# meow-65.net
KiCad netlist of a schematic drawn in Altium Designer
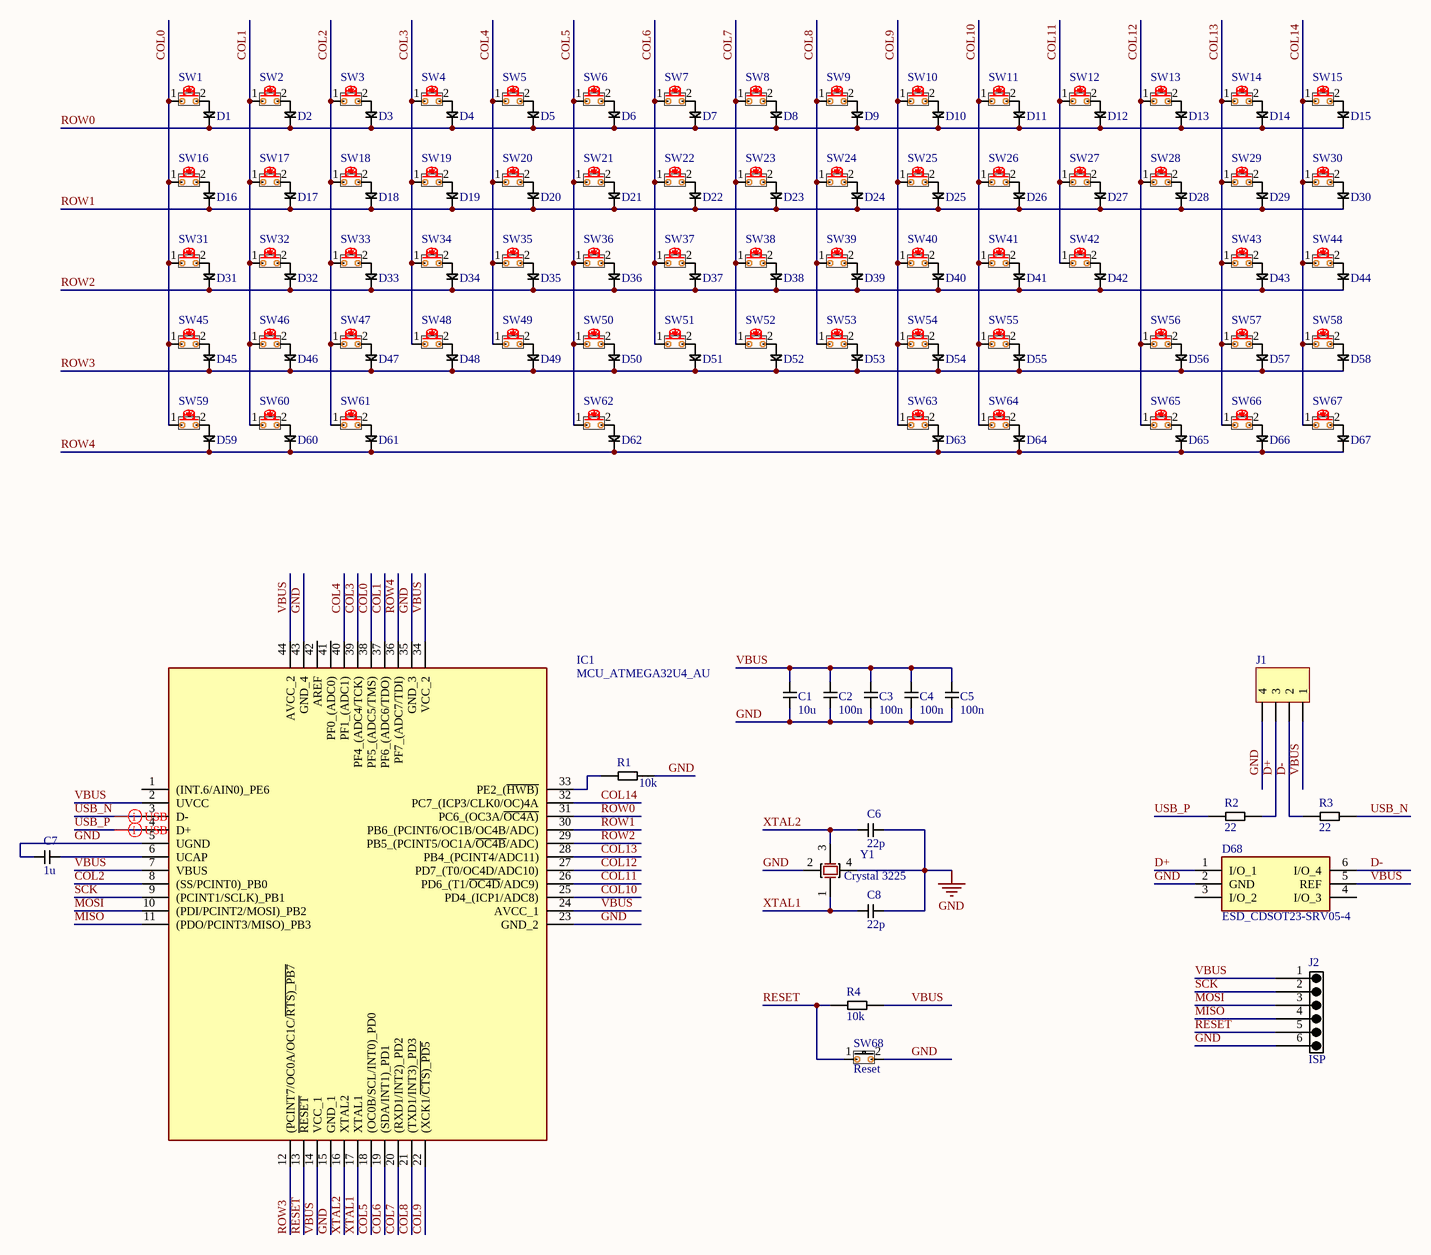
[diagram p0: meow-65.SchDoc]

(export (version "E")
  (design (tool "Eeschema 10.0.6"))
  (components
    (comp (ref "C1") (value "10u") (footprint "CAP_0805") (libsource (lib "Keyboard") (part "CAP_0805")))
    (comp (ref "C2") (value "100n") (footprint "CAP_0805") (libsource (lib "Keyboard") (part "CAP_0805")))
    (comp (ref "C3") (value "100n") (footprint "CAP_0805") (libsource (lib "Keyboard") (part "CAP_0805")))
    (comp (ref "C4") (value "100n") (footprint "CAP_0805") (libsource (lib "Keyboard") (part "CAP_0805")))
    (comp (ref "C5") (value "100n") (footprint "CAP_0805") (libsource (lib "Keyboard") (part "CAP_0805")))
    (comp (ref "C6") (value "22p") (footprint "CAP_0805") (libsource (lib "Keyboard") (part "CAP_0805")))
    (comp (ref "C7") (value "1u") (footprint "CAP_0805") (libsource (lib "Keyboard") (part "CAP_0805")))
    (comp (ref "C8") (value "22p") (footprint "CAP_0805") (libsource (lib "Keyboard") (part "CAP_0805")))
    (comp (ref "D1")
      (value "1N4148_SOD123")
      (footprint "SOD123")
      (libsource (lib "Keyboard") (part "1N4148_SOD123"))
    )
    (comp (ref "D2")
      (value "1N4148_SOD123")
      (footprint "SOD123")
      (libsource (lib "Keyboard") (part "1N4148_SOD123"))
    )
    (comp (ref "D3")
      (value "1N4148_SOD123")
      (footprint "SOD123")
      (libsource (lib "Keyboard") (part "1N4148_SOD123"))
    )
    (comp (ref "D4")
      (value "1N4148_SOD123")
      (footprint "SOD123")
      (libsource (lib "Keyboard") (part "1N4148_SOD123"))
    )
    (comp (ref "D5")
      (value "1N4148_SOD123")
      (footprint "SOD123")
      (libsource (lib "Keyboard") (part "1N4148_SOD123"))
    )
    (comp (ref "D6")
      (value "1N4148_SOD123")
      (footprint "SOD123")
      (libsource (lib "Keyboard") (part "1N4148_SOD123"))
    )
    (comp (ref "D7")
      (value "1N4148_SOD123")
      (footprint "SOD123")
      (libsource (lib "Keyboard") (part "1N4148_SOD123"))
    )
    (comp (ref "D8")
      (value "1N4148_SOD123")
      (footprint "SOD123")
      (libsource (lib "Keyboard") (part "1N4148_SOD123"))
    )
    (comp (ref "D9")
      (value "1N4148_SOD123")
      (footprint "SOD123")
      (libsource (lib "Keyboard") (part "1N4148_SOD123"))
    )
    (comp (ref "D10")
      (value "1N4148_SOD123")
      (footprint "SOD123")
      (libsource (lib "Keyboard") (part "1N4148_SOD123"))
    )
    (comp (ref "D11")
      (value "1N4148_SOD123")
      (footprint "SOD123")
      (libsource (lib "Keyboard") (part "1N4148_SOD123"))
    )
    (comp (ref "D12")
      (value "1N4148_SOD123")
      (footprint "SOD123")
      (libsource (lib "Keyboard") (part "1N4148_SOD123"))
    )
    (comp (ref "D13")
      (value "1N4148_SOD123")
      (footprint "SOD123")
      (libsource (lib "Keyboard") (part "1N4148_SOD123"))
    )
    (comp (ref "D14")
      (value "1N4148_SOD123")
      (footprint "SOD123")
      (libsource (lib "Keyboard") (part "1N4148_SOD123"))
    )
    (comp (ref "D15")
      (value "1N4148_SOD123")
      (footprint "SOD123")
      (libsource (lib "Keyboard") (part "1N4148_SOD123"))
    )
    (comp (ref "D16")
      (value "1N4148_SOD123")
      (footprint "SOD123")
      (libsource (lib "Keyboard") (part "1N4148_SOD123"))
    )
    (comp (ref "D17")
      (value "1N4148_SOD123")
      (footprint "SOD123")
      (libsource (lib "Keyboard") (part "1N4148_SOD123"))
    )
    (comp (ref "D18")
      (value "1N4148_SOD123")
      (footprint "SOD123")
      (libsource (lib "Keyboard") (part "1N4148_SOD123"))
    )
    (comp (ref "D19")
      (value "1N4148_SOD123")
      (footprint "SOD123")
      (libsource (lib "Keyboard") (part "1N4148_SOD123"))
    )
    (comp (ref "D20")
      (value "1N4148_SOD123")
      (footprint "SOD123")
      (libsource (lib "Keyboard") (part "1N4148_SOD123"))
    )
    (comp (ref "D21")
      (value "1N4148_SOD123")
      (footprint "SOD123")
      (libsource (lib "Keyboard") (part "1N4148_SOD123"))
    )
    (comp (ref "D22")
      (value "1N4148_SOD123")
      (footprint "SOD123")
      (libsource (lib "Keyboard") (part "1N4148_SOD123"))
    )
    (comp (ref "D23")
      (value "1N4148_SOD123")
      (footprint "SOD123")
      (libsource (lib "Keyboard") (part "1N4148_SOD123"))
    )
    (comp (ref "D24")
      (value "1N4148_SOD123")
      (footprint "SOD123")
      (libsource (lib "Keyboard") (part "1N4148_SOD123"))
    )
    (comp (ref "D25")
      (value "1N4148_SOD123")
      (footprint "SOD123")
      (libsource (lib "Keyboard") (part "1N4148_SOD123"))
    )
    (comp (ref "D26")
      (value "1N4148_SOD123")
      (footprint "SOD123")
      (libsource (lib "Keyboard") (part "1N4148_SOD123"))
    )
    (comp (ref "D27")
      (value "1N4148_SOD123")
      (footprint "SOD123")
      (libsource (lib "Keyboard") (part "1N4148_SOD123"))
    )
    (comp (ref "D28")
      (value "1N4148_SOD123")
      (footprint "SOD123")
      (libsource (lib "Keyboard") (part "1N4148_SOD123"))
    )
    (comp (ref "D29")
      (value "1N4148_SOD123")
      (footprint "SOD123")
      (libsource (lib "Keyboard") (part "1N4148_SOD123"))
    )
    (comp (ref "D30")
      (value "1N4148_SOD123")
      (footprint "SOD123")
      (libsource (lib "Keyboard") (part "1N4148_SOD123"))
    )
    (comp (ref "D31")
      (value "1N4148_SOD123")
      (footprint "SOD123")
      (libsource (lib "Keyboard") (part "1N4148_SOD123"))
    )
    (comp (ref "D32")
      (value "1N4148_SOD123")
      (footprint "SOD123")
      (libsource (lib "Keyboard") (part "1N4148_SOD123"))
    )
    (comp (ref "D33")
      (value "1N4148_SOD123")
      (footprint "SOD123")
      (libsource (lib "Keyboard") (part "1N4148_SOD123"))
    )
    (comp (ref "D34")
      (value "1N4148_SOD123")
      (footprint "SOD123")
      (libsource (lib "Keyboard") (part "1N4148_SOD123"))
    )
    (comp (ref "D35")
      (value "1N4148_SOD123")
      (footprint "SOD123")
      (libsource (lib "Keyboard") (part "1N4148_SOD123"))
    )
    (comp (ref "D36")
      (value "1N4148_SOD123")
      (footprint "SOD123")
      (libsource (lib "Keyboard") (part "1N4148_SOD123"))
    )
    (comp (ref "D37")
      (value "1N4148_SOD123")
      (footprint "SOD123")
      (libsource (lib "Keyboard") (part "1N4148_SOD123"))
    )
    (comp (ref "D38")
      (value "1N4148_SOD123")
      (footprint "SOD123")
      (libsource (lib "Keyboard") (part "1N4148_SOD123"))
    )
    (comp (ref "D39")
      (value "1N4148_SOD123")
      (footprint "SOD123")
      (libsource (lib "Keyboard") (part "1N4148_SOD123"))
    )
    (comp (ref "D40")
      (value "1N4148_SOD123")
      (footprint "SOD123")
      (libsource (lib "Keyboard") (part "1N4148_SOD123"))
    )
    (comp (ref "D41")
      (value "1N4148_SOD123")
      (footprint "SOD123")
      (libsource (lib "Keyboard") (part "1N4148_SOD123"))
    )
    (comp (ref "D42")
      (value "1N4148_SOD123")
      (footprint "SOD123")
      (libsource (lib "Keyboard") (part "1N4148_SOD123"))
    )
    (comp (ref "D43")
      (value "1N4148_SOD123")
      (footprint "SOD123")
      (libsource (lib "Keyboard") (part "1N4148_SOD123"))
    )
    (comp (ref "D44")
      (value "1N4148_SOD123")
      (footprint "SOD123")
      (libsource (lib "Keyboard") (part "1N4148_SOD123"))
    )
    (comp (ref "D45")
      (value "1N4148_SOD123")
      (footprint "SOD123")
      (libsource (lib "Keyboard") (part "1N4148_SOD123"))
    )
    (comp (ref "D46")
      (value "1N4148_SOD123")
      (footprint "SOD123")
      (libsource (lib "Keyboard") (part "1N4148_SOD123"))
    )
    (comp (ref "D47")
      (value "1N4148_SOD123")
      (footprint "SOD123")
      (libsource (lib "Keyboard") (part "1N4148_SOD123"))
    )
    (comp (ref "D48")
      (value "1N4148_SOD123")
      (footprint "SOD123")
      (libsource (lib "Keyboard") (part "1N4148_SOD123"))
    )
    (comp (ref "D49")
      (value "1N4148_SOD123")
      (footprint "SOD123")
      (libsource (lib "Keyboard") (part "1N4148_SOD123"))
    )
    (comp (ref "D50")
      (value "1N4148_SOD123")
      (footprint "SOD123")
      (libsource (lib "Keyboard") (part "1N4148_SOD123"))
    )
    (comp (ref "D51")
      (value "1N4148_SOD123")
      (footprint "SOD123")
      (libsource (lib "Keyboard") (part "1N4148_SOD123"))
    )
    (comp (ref "D52")
      (value "1N4148_SOD123")
      (footprint "SOD123")
      (libsource (lib "Keyboard") (part "1N4148_SOD123"))
    )
    (comp (ref "D53")
      (value "1N4148_SOD123")
      (footprint "SOD123")
      (libsource (lib "Keyboard") (part "1N4148_SOD123"))
    )
    (comp (ref "D54")
      (value "1N4148_SOD123")
      (footprint "SOD123")
      (libsource (lib "Keyboard") (part "1N4148_SOD123"))
    )
    (comp (ref "D55")
      (value "1N4148_SOD123")
      (footprint "SOD123")
      (libsource (lib "Keyboard") (part "1N4148_SOD123"))
    )
    (comp (ref "D56")
      (value "1N4148_SOD123")
      (footprint "SOD123")
      (libsource (lib "Keyboard") (part "1N4148_SOD123"))
    )
    (comp (ref "D57")
      (value "1N4148_SOD123")
      (footprint "SOD123")
      (libsource (lib "Keyboard") (part "1N4148_SOD123"))
    )
    (comp (ref "D58")
      (value "1N4148_SOD123")
      (footprint "SOD123")
      (libsource (lib "Keyboard") (part "1N4148_SOD123"))
    )
    (comp (ref "D59")
      (value "1N4148_SOD123")
      (footprint "SOD123")
      (libsource (lib "Keyboard") (part "1N4148_SOD123"))
    )
    (comp (ref "D60")
      (value "1N4148_SOD123")
      (footprint "SOD123")
      (libsource (lib "Keyboard") (part "1N4148_SOD123"))
    )
    (comp (ref "D61")
      (value "1N4148_SOD123")
      (footprint "SOD123")
      (libsource (lib "Keyboard") (part "1N4148_SOD123"))
    )
    (comp (ref "D62")
      (value "1N4148_SOD123")
      (footprint "SOD123")
      (libsource (lib "Keyboard") (part "1N4148_SOD123"))
    )
    (comp (ref "D63")
      (value "1N4148_SOD123")
      (footprint "SOD123")
      (libsource (lib "Keyboard") (part "1N4148_SOD123"))
    )
    (comp (ref "D64")
      (value "1N4148_SOD123")
      (footprint "SOD123")
      (libsource (lib "Keyboard") (part "1N4148_SOD123"))
    )
    (comp (ref "D65")
      (value "1N4148_SOD123")
      (footprint "SOD123")
      (libsource (lib "Keyboard") (part "1N4148_SOD123"))
    )
    (comp (ref "D66")
      (value "1N4148_SOD123")
      (footprint "SOD123")
      (libsource (lib "Keyboard") (part "1N4148_SOD123"))
    )
    (comp (ref "D67")
      (value "1N4148_SOD123")
      (footprint "SOD123")
      (libsource (lib "Keyboard") (part "1N4148_SOD123"))
    )
    (comp (ref "D68")
      (value "ESD_CDSOT23-SRV05-4")
      (footprint "SOT23_6")
      (libsource (lib "Keyboard") (part "ESD_CDSOT23-SRV05-4"))
    )
    (comp (ref "IC1")
      (value "MCU_ATMEGA32U4_AU")
      (footprint "44-TQFP")
      (libsource (lib "Keyboard") (part "MCU_ATMEGA32U4_AU"))
    )
    (comp (ref "J1")
      (value "SM04B-SRSS-TB(LF)(SN)")
      (footprint "JP_1.0_4P")
      (libsource (lib "Keyboard") (part "JP_1.0_4P"))
    )
    (comp (ref "J2")
      (value "ISP")
      (footprint "JP_2.54_6P_NoJump")
      (libsource (lib "Keyboard") (part "JP_2.54_6P_NoJump"))
    )
    (comp (ref "R1") (value "10k") (footprint "RES_0805") (libsource (lib "Keyboard") (part "RES_0805")))
    (comp (ref "R2") (value "22") (footprint "RES_0805") (libsource (lib "Keyboard") (part "RES_0805")))
    (comp (ref "R3") (value "22") (footprint "RES_0805") (libsource (lib "Keyboard") (part "RES_0805")))
    (comp (ref "R4") (value "10k") (footprint "RES_0805") (libsource (lib "Keyboard") (part "RES_0805")))
    (comp (ref "SW1") (value "MX_HS") (footprint "MX_HS") (libsource (lib "Keyboard") (part "MX_HS")))
    (comp (ref "SW2") (value "MX_HS") (footprint "MX_HS") (libsource (lib "Keyboard") (part "MX_HS")))
    (comp (ref "SW3") (value "MX_HS") (footprint "MX_HS") (libsource (lib "Keyboard") (part "MX_HS")))
    (comp (ref "SW4") (value "MX_HS") (footprint "MX_HS") (libsource (lib "Keyboard") (part "MX_HS")))
    (comp (ref "SW5") (value "MX_HS") (footprint "MX_HS") (libsource (lib "Keyboard") (part "MX_HS")))
    (comp (ref "SW6") (value "MX_HS") (footprint "MX_HS") (libsource (lib "Keyboard") (part "MX_HS")))
    (comp (ref "SW7") (value "MX_HS") (footprint "MX_HS") (libsource (lib "Keyboard") (part "MX_HS")))
    (comp (ref "SW8") (value "MX_HS") (footprint "MX_HS") (libsource (lib "Keyboard") (part "MX_HS")))
    (comp (ref "SW9") (value "MX_HS") (footprint "MX_HS") (libsource (lib "Keyboard") (part "MX_HS")))
    (comp (ref "SW10") (value "MX_HS") (footprint "MX_HS") (libsource (lib "Keyboard") (part "MX_HS")))
    (comp (ref "SW11") (value "MX_HS") (footprint "MX_HS") (libsource (lib "Keyboard") (part "MX_HS")))
    (comp (ref "SW12") (value "MX_HS") (footprint "MX_HS") (libsource (lib "Keyboard") (part "MX_HS")))
    (comp (ref "SW13") (value "MX_HS") (footprint "MX_HS") (libsource (lib "Keyboard") (part "MX_HS")))
    (comp (ref "SW14")
      (value "MX_HS_2U")
      (footprint "MX_HS_2U")
      (libsource (lib "Keyboard") (part "MX_HS_2U"))
    )
    (comp (ref "SW15") (value "MX_HS") (footprint "MX_HS") (libsource (lib "Keyboard") (part "MX_HS")))
    (comp (ref "SW16") (value "MX_HS") (footprint "MX_HS") (libsource (lib "Keyboard") (part "MX_HS")))
    (comp (ref "SW17") (value "MX_HS") (footprint "MX_HS") (libsource (lib "Keyboard") (part "MX_HS")))
    (comp (ref "SW18") (value "MX_HS") (footprint "MX_HS") (libsource (lib "Keyboard") (part "MX_HS")))
    (comp (ref "SW19") (value "MX_HS") (footprint "MX_HS") (libsource (lib "Keyboard") (part "MX_HS")))
    (comp (ref "SW20") (value "MX_HS") (footprint "MX_HS") (libsource (lib "Keyboard") (part "MX_HS")))
    (comp (ref "SW21") (value "MX_HS") (footprint "MX_HS") (libsource (lib "Keyboard") (part "MX_HS")))
    (comp (ref "SW22") (value "MX_HS") (footprint "MX_HS") (libsource (lib "Keyboard") (part "MX_HS")))
    (comp (ref "SW23") (value "MX_HS") (footprint "MX_HS") (libsource (lib "Keyboard") (part "MX_HS")))
    (comp (ref "SW24") (value "MX_HS") (footprint "MX_HS") (libsource (lib "Keyboard") (part "MX_HS")))
    (comp (ref "SW25") (value "MX_HS") (footprint "MX_HS") (libsource (lib "Keyboard") (part "MX_HS")))
    (comp (ref "SW26") (value "MX_HS") (footprint "MX_HS") (libsource (lib "Keyboard") (part "MX_HS")))
    (comp (ref "SW27") (value "MX_HS") (footprint "MX_HS") (libsource (lib "Keyboard") (part "MX_HS")))
    (comp (ref "SW28") (value "MX_HS") (footprint "MX_HS") (libsource (lib "Keyboard") (part "MX_HS")))
    (comp (ref "SW29") (value "MX_HS") (footprint "MX_HS") (libsource (lib "Keyboard") (part "MX_HS")))
    (comp (ref "SW30") (value "MX_HS") (footprint "MX_HS") (libsource (lib "Keyboard") (part "MX_HS")))
    (comp (ref "SW31") (value "MX_HS") (footprint "MX_HS") (libsource (lib "Keyboard") (part "MX_HS")))
    (comp (ref "SW32") (value "MX_HS") (footprint "MX_HS") (libsource (lib "Keyboard") (part "MX_HS")))
    (comp (ref "SW33") (value "MX_HS") (footprint "MX_HS") (libsource (lib "Keyboard") (part "MX_HS")))
    (comp (ref "SW34") (value "MX_HS") (footprint "MX_HS") (libsource (lib "Keyboard") (part "MX_HS")))
    (comp (ref "SW35") (value "MX_HS") (footprint "MX_HS") (libsource (lib "Keyboard") (part "MX_HS")))
    (comp (ref "SW36") (value "MX_HS") (footprint "MX_HS") (libsource (lib "Keyboard") (part "MX_HS")))
    (comp (ref "SW37") (value "MX_HS") (footprint "MX_HS") (libsource (lib "Keyboard") (part "MX_HS")))
    (comp (ref "SW38") (value "MX_HS") (footprint "MX_HS") (libsource (lib "Keyboard") (part "MX_HS")))
    (comp (ref "SW39") (value "MX_HS") (footprint "MX_HS") (libsource (lib "Keyboard") (part "MX_HS")))
    (comp (ref "SW40") (value "MX_HS") (footprint "MX_HS") (libsource (lib "Keyboard") (part "MX_HS")))
    (comp (ref "SW41") (value "MX_HS") (footprint "MX_HS") (libsource (lib "Keyboard") (part "MX_HS")))
    (comp (ref "SW42") (value "MX_HS") (footprint "MX_HS") (libsource (lib "Keyboard") (part "MX_HS")))
    (comp (ref "SW43")
      (value "MX_HS_2U")
      (footprint "MX_HS_2U")
      (libsource (lib "Keyboard") (part "MX_HS_2U"))
    )
    (comp (ref "SW44") (value "MX_HS") (footprint "MX_HS") (libsource (lib "Keyboard") (part "MX_HS")))
    (comp (ref "SW45")
      (value "MX_HS_2U")
      (footprint "MX_HS_2U")
      (libsource (lib "Keyboard") (part "MX_HS_2U"))
    )
    (comp (ref "SW46") (value "MX_HS") (footprint "MX_HS") (libsource (lib "Keyboard") (part "MX_HS")))
    (comp (ref "SW47") (value "MX_HS") (footprint "MX_HS") (libsource (lib "Keyboard") (part "MX_HS")))
    (comp (ref "SW48") (value "MX_HS") (footprint "MX_HS") (libsource (lib "Keyboard") (part "MX_HS")))
    (comp (ref "SW49") (value "MX_HS") (footprint "MX_HS") (libsource (lib "Keyboard") (part "MX_HS")))
    (comp (ref "SW50") (value "MX_HS") (footprint "MX_HS") (libsource (lib "Keyboard") (part "MX_HS")))
    (comp (ref "SW51") (value "MX_HS") (footprint "MX_HS") (libsource (lib "Keyboard") (part "MX_HS")))
    (comp (ref "SW52") (value "MX_HS") (footprint "MX_HS") (libsource (lib "Keyboard") (part "MX_HS")))
    (comp (ref "SW53") (value "MX_HS") (footprint "MX_HS") (libsource (lib "Keyboard") (part "MX_HS")))
    (comp (ref "SW54") (value "MX_HS") (footprint "MX_HS") (libsource (lib "Keyboard") (part "MX_HS")))
    (comp (ref "SW55") (value "MX_HS") (footprint "MX_HS") (libsource (lib "Keyboard") (part "MX_HS")))
    (comp (ref "SW56") (value "MX_HS") (footprint "MX_HS") (libsource (lib "Keyboard") (part "MX_HS")))
    (comp (ref "SW57") (value "MX_HS") (footprint "MX_HS") (libsource (lib "Keyboard") (part "MX_HS")))
    (comp (ref "SW58") (value "MX_HS") (footprint "MX_HS") (libsource (lib "Keyboard") (part "MX_HS")))
    (comp (ref "SW59") (value "MX_HS") (footprint "MX_HS") (libsource (lib "Keyboard") (part "MX_HS")))
    (comp (ref "SW60") (value "MX_HS") (footprint "MX_HS") (libsource (lib "Keyboard") (part "MX_HS")))
    (comp (ref "SW61") (value "MX_HS") (footprint "MX_HS") (libsource (lib "Keyboard") (part "MX_HS")))
    (comp (ref "SW62")
      (value "MX_HS_6.25u")
      (footprint "MX_HS_6.25U")
      (libsource (lib "Keyboard") (part "MX_HS_6.25u"))
    )
    (comp (ref "SW63") (value "MX_HS") (footprint "MX_HS") (libsource (lib "Keyboard") (part "MX_HS")))
    (comp (ref "SW64") (value "MX_HS") (footprint "MX_HS") (libsource (lib "Keyboard") (part "MX_HS")))
    (comp (ref "SW65") (value "MX_HS") (footprint "MX_HS") (libsource (lib "Keyboard") (part "MX_HS")))
    (comp (ref "SW66") (value "MX_HS") (footprint "MX_HS") (libsource (lib "Keyboard") (part "MX_HS")))
    (comp (ref "SW67") (value "MX_HS") (footprint "MX_HS") (libsource (lib "Keyboard") (part "MX_HS")))
    (comp (ref "SW68") (value "Reset") (footprint "SW_5.2MM") (libsource (lib "Keyboard") (part "SW_5.2mm")))
    (comp (ref "Y1")
      (value "Crystal 3225")
      (footprint "Crystal-3225")
      (libsource (lib "Keyboard") (part "Crystal 3225"))
    )
  )
  (nets
    (net (code "1") (name "/COL0") (class "Default")
      (node (ref "IC1") (pin "38") (pinfunction "PF5_(ADC5/TMS)_38") (pintype "passive"))
      (node (ref "SW1") (pin "1") (pinfunction "7_1") (pintype "passive"))
      (node (ref "SW16") (pin "1") (pinfunction "7_1") (pintype "passive"))
      (node (ref "SW31") (pin "1") (pinfunction "7_1") (pintype "passive"))
      (node (ref "SW45") (pin "1") (pinfunction "7_1") (pintype "passive"))
      (node (ref "SW59") (pin "1") (pinfunction "7_1") (pintype "passive"))
    )
    (net (code "2") (name "/COL1") (class "Default")
      (node (ref "IC1") (pin "37") (pinfunction "PF6_(ADC6/TDO)_37") (pintype "passive"))
      (node (ref "SW17") (pin "1") (pinfunction "7_1") (pintype "passive"))
      (node (ref "SW2") (pin "1") (pinfunction "7_1") (pintype "passive"))
      (node (ref "SW32") (pin "1") (pinfunction "7_1") (pintype "passive"))
      (node (ref "SW46") (pin "1") (pinfunction "7_1") (pintype "passive"))
      (node (ref "SW60") (pin "1") (pinfunction "7_1") (pintype "passive"))
    )
    (net (code "3") (name "/COL2") (class "Default")
      (node (ref "IC1") (pin "8") (pinfunction "(SS/PCINT0)_PB0_8") (pintype "passive"))
      (node (ref "SW18") (pin "1") (pinfunction "7_1") (pintype "passive"))
      (node (ref "SW3") (pin "1") (pinfunction "7_1") (pintype "passive"))
      (node (ref "SW33") (pin "1") (pinfunction "7_1") (pintype "passive"))
      (node (ref "SW47") (pin "1") (pinfunction "7_1") (pintype "passive"))
      (node (ref "SW61") (pin "1") (pinfunction "7_1") (pintype "passive"))
    )
    (net (code "4") (name "/COL3") (class "Default")
      (node (ref "IC1") (pin "39") (pinfunction "PF4_(ADC4/TCK)_39") (pintype "passive"))
      (node (ref "SW19") (pin "1") (pinfunction "7_1") (pintype "passive"))
      (node (ref "SW34") (pin "1") (pinfunction "7_1") (pintype "passive"))
      (node (ref "SW4") (pin "1") (pinfunction "7_1") (pintype "passive"))
      (node (ref "SW48") (pin "1") (pinfunction "7_1") (pintype "passive"))
    )
    (net (code "5") (name "/COL4") (class "Default")
      (node (ref "IC1") (pin "40") (pinfunction "PF1_(ADC1)_40") (pintype "passive"))
      (node (ref "SW20") (pin "1") (pinfunction "7_1") (pintype "passive"))
      (node (ref "SW35") (pin "1") (pinfunction "7_1") (pintype "passive"))
      (node (ref "SW49") (pin "1") (pinfunction "7_1") (pintype "passive"))
      (node (ref "SW5") (pin "1") (pinfunction "7_1") (pintype "passive"))
    )
    (net (code "6") (name "/COL5") (class "Default")
      (node (ref "IC1") (pin "18") (pinfunction "(OC0B/SCL/INT0)_PD0_18") (pintype "passive"))
      (node (ref "SW21") (pin "1") (pinfunction "7_1") (pintype "passive"))
      (node (ref "SW36") (pin "1") (pinfunction "7_1") (pintype "passive"))
      (node (ref "SW50") (pin "1") (pinfunction "7_1") (pintype "passive"))
      (node (ref "SW6") (pin "1") (pinfunction "7_1") (pintype "passive"))
      (node (ref "SW62") (pin "1") (pinfunction "7_1") (pintype "passive"))
    )
    (net (code "7") (name "/COL6") (class "Default")
      (node (ref "IC1") (pin "19") (pinfunction "(SDA/INT1)_PD1_19") (pintype "passive"))
      (node (ref "SW22") (pin "1") (pinfunction "7_1") (pintype "passive"))
      (node (ref "SW37") (pin "1") (pinfunction "7_1") (pintype "passive"))
      (node (ref "SW51") (pin "1") (pinfunction "7_1") (pintype "passive"))
      (node (ref "SW7") (pin "1") (pinfunction "7_1") (pintype "passive"))
    )
    (net (code "8") (name "/COL7") (class "Default")
      (node (ref "IC1") (pin "20") (pinfunction "(RXD1/INT2)_PD2_20") (pintype "passive"))
      (node (ref "SW23") (pin "1") (pinfunction "7_1") (pintype "passive"))
      (node (ref "SW38") (pin "1") (pinfunction "7_1") (pintype "passive"))
      (node (ref "SW52") (pin "1") (pinfunction "7_1") (pintype "passive"))
      (node (ref "SW8") (pin "1") (pinfunction "7_1") (pintype "passive"))
    )
    (net (code "9") (name "/COL8") (class "Default")
      (node (ref "IC1") (pin "21") (pinfunction "(TXD1/INT3)_PD3_21") (pintype "passive"))
      (node (ref "SW24") (pin "1") (pinfunction "7_1") (pintype "passive"))
      (node (ref "SW39") (pin "1") (pinfunction "7_1") (pintype "passive"))
      (node (ref "SW53") (pin "1") (pinfunction "7_1") (pintype "passive"))
      (node (ref "SW9") (pin "1") (pinfunction "7_1") (pintype "passive"))
    )
    (net (code "10") (name "/COL9") (class "Default")
      (node (ref "IC1") (pin "22") (pinfunction "(XCK1/~{CTS)_PD5}_22") (pintype "passive"))
      (node (ref "SW10") (pin "1") (pinfunction "7_1") (pintype "passive"))
      (node (ref "SW25") (pin "1") (pinfunction "7_1") (pintype "passive"))
      (node (ref "SW40") (pin "1") (pinfunction "7_1") (pintype "passive"))
      (node (ref "SW54") (pin "1") (pinfunction "7_1") (pintype "passive"))
      (node (ref "SW63") (pin "1") (pinfunction "7_1") (pintype "passive"))
    )
    (net (code "11") (name "/COL10") (class "Default")
      (node (ref "IC1") (pin "25") (pinfunction "PD4_(ICP1/ADC8)_25") (pintype "passive"))
      (node (ref "SW11") (pin "1") (pinfunction "7_1") (pintype "passive"))
      (node (ref "SW26") (pin "1") (pinfunction "7_1") (pintype "passive"))
      (node (ref "SW41") (pin "1") (pinfunction "7_1") (pintype "passive"))
      (node (ref "SW55") (pin "1") (pinfunction "7_1") (pintype "passive"))
      (node (ref "SW64") (pin "1") (pinfunction "7_1") (pintype "passive"))
    )
    (net (code "12") (name "/COL11") (class "Default")
      (node (ref "IC1") (pin "26") (pinfunction "PD6_(T1/~{OC4D}/ADC9)_26") (pintype "passive"))
      (node (ref "SW12") (pin "1") (pinfunction "7_1") (pintype "passive"))
      (node (ref "SW27") (pin "1") (pinfunction "7_1") (pintype "passive"))
      (node (ref "SW42") (pin "1") (pinfunction "7_1") (pintype "passive"))
    )
    (net (code "13") (name "/COL12") (class "Default")
      (node (ref "IC1") (pin "27") (pinfunction "PD7_(T0/OC4D/ADC10)_27") (pintype "passive"))
      (node (ref "SW13") (pin "1") (pinfunction "7_1") (pintype "passive"))
      (node (ref "SW28") (pin "1") (pinfunction "7_1") (pintype "passive"))
      (node (ref "SW56") (pin "1") (pinfunction "7_1") (pintype "passive"))
      (node (ref "SW65") (pin "1") (pinfunction "7_1") (pintype "passive"))
    )
    (net (code "14") (name "/COL13") (class "Default")
      (node (ref "IC1") (pin "28") (pinfunction "PB4_(PCINT4/ADC11)_28") (pintype "passive"))
      (node (ref "SW14") (pin "1") (pinfunction "7_1") (pintype "passive"))
      (node (ref "SW29") (pin "1") (pinfunction "7_1") (pintype "passive"))
      (node (ref "SW43") (pin "1") (pinfunction "7_1") (pintype "passive"))
      (node (ref "SW57") (pin "1") (pinfunction "7_1") (pintype "passive"))
      (node (ref "SW66") (pin "1") (pinfunction "7_1") (pintype "passive"))
    )
    (net (code "15") (name "/COL14") (class "Default")
      (node (ref "IC1") (pin "32") (pinfunction "PC7_(ICP3/CLK0/OC)4A_32") (pintype "passive"))
      (node (ref "SW15") (pin "1") (pinfunction "7_1") (pintype "passive"))
      (node (ref "SW30") (pin "1") (pinfunction "7_1") (pintype "passive"))
      (node (ref "SW44") (pin "1") (pinfunction "7_1") (pintype "passive"))
      (node (ref "SW58") (pin "1") (pinfunction "7_1") (pintype "passive"))
      (node (ref "SW67") (pin "1") (pinfunction "7_1") (pintype "passive"))
    )
    (net (code "16") (name "/D+") (class "Default")
      (node (ref "D68") (pin "1") (pinfunction "I/O_1_1") (pintype "passive"))
      (node (ref "J1") (pin "3") (pinfunction "3_3") (pintype "passive"))
      (node (ref "R2") (pin "2") (pinfunction "2_2") (pintype "passive"))
    )
    (net (code "17") (name "/D-") (class "Default")
      (node (ref "D68") (pin "6") (pinfunction "I/O_4_6") (pintype "passive"))
      (node (ref "J1") (pin "2") (pinfunction "2_2") (pintype "passive"))
      (node (ref "R3") (pin "1") (pinfunction "1_1") (pintype "passive"))
    )
    (net (code "18") (name "/MISO") (class "Default")
      (node (ref "IC1") (pin "11") (pinfunction "(PDO/PCINT3/MISO)_PB3_11") (pintype "passive"))
      (node (ref "J2") (pin "4") (pintype "passive"))
    )
    (net (code "19") (name "/MOSI") (class "Default")
      (node (ref "IC1") (pin "10") (pinfunction "(PDI/PCINT2/MOSI)_PB2_10") (pintype "passive"))
      (node (ref "J2") (pin "3") (pintype "passive"))
    )
    (net (code "20") (name "/RESET") (class "Default")
      (node (ref "IC1") (pin "13") (pinfunction "~{RESET}_13") (pintype "passive"))
      (node (ref "J2") (pin "5") (pintype "passive"))
      (node (ref "R4") (pin "1") (pinfunction "1_1") (pintype "passive"))
      (node (ref "SW68") (pin "1") (pinfunction "7_1") (pintype "passive"))
    )
    (net (code "21") (name "/ROW0") (class "Default")
      (node (ref "D1") (pin "2") (pinfunction "2_2") (pintype "passive"))
      (node (ref "D10") (pin "2") (pinfunction "2_2") (pintype "passive"))
      (node (ref "D11") (pin "2") (pinfunction "2_2") (pintype "passive"))
      (node (ref "D12") (pin "2") (pinfunction "2_2") (pintype "passive"))
      (node (ref "D13") (pin "2") (pinfunction "2_2") (pintype "passive"))
      (node (ref "D14") (pin "2") (pinfunction "2_2") (pintype "passive"))
      (node (ref "D15") (pin "2") (pinfunction "2_2") (pintype "passive"))
      (node (ref "D2") (pin "2") (pinfunction "2_2") (pintype "passive"))
      (node (ref "D3") (pin "2") (pinfunction "2_2") (pintype "passive"))
      (node (ref "D4") (pin "2") (pinfunction "2_2") (pintype "passive"))
      (node (ref "D5") (pin "2") (pinfunction "2_2") (pintype "passive"))
      (node (ref "D6") (pin "2") (pinfunction "2_2") (pintype "passive"))
      (node (ref "D7") (pin "2") (pinfunction "2_2") (pintype "passive"))
      (node (ref "D8") (pin "2") (pinfunction "2_2") (pintype "passive"))
      (node (ref "D9") (pin "2") (pinfunction "2_2") (pintype "passive"))
      (node (ref "IC1") (pin "31") (pinfunction "PC6_(OC3A/~{OC4A)}_31") (pintype "passive"))
    )
    (net (code "22") (name "/ROW1") (class "Default")
      (node (ref "D16") (pin "2") (pinfunction "2_2") (pintype "passive"))
      (node (ref "D17") (pin "2") (pinfunction "2_2") (pintype "passive"))
      (node (ref "D18") (pin "2") (pinfunction "2_2") (pintype "passive"))
      (node (ref "D19") (pin "2") (pinfunction "2_2") (pintype "passive"))
      (node (ref "D20") (pin "2") (pinfunction "2_2") (pintype "passive"))
      (node (ref "D21") (pin "2") (pinfunction "2_2") (pintype "passive"))
      (node (ref "D22") (pin "2") (pinfunction "2_2") (pintype "passive"))
      (node (ref "D23") (pin "2") (pinfunction "2_2") (pintype "passive"))
      (node (ref "D24") (pin "2") (pinfunction "2_2") (pintype "passive"))
      (node (ref "D25") (pin "2") (pinfunction "2_2") (pintype "passive"))
      (node (ref "D26") (pin "2") (pinfunction "2_2") (pintype "passive"))
      (node (ref "D27") (pin "2") (pinfunction "2_2") (pintype "passive"))
      (node (ref "D28") (pin "2") (pinfunction "2_2") (pintype "passive"))
      (node (ref "D29") (pin "2") (pinfunction "2_2") (pintype "passive"))
      (node (ref "D30") (pin "2") (pinfunction "2_2") (pintype "passive"))
      (node (ref "IC1") (pin "30") (pinfunction "PB6_(PCINT6/OC1B/OC4B/ADC)_30") (pintype "passive"))
    )
    (net (code "23") (name "/ROW2") (class "Default")
      (node (ref "D31") (pin "2") (pinfunction "2_2") (pintype "passive"))
      (node (ref "D32") (pin "2") (pinfunction "2_2") (pintype "passive"))
      (node (ref "D33") (pin "2") (pinfunction "2_2") (pintype "passive"))
      (node (ref "D34") (pin "2") (pinfunction "2_2") (pintype "passive"))
      (node (ref "D35") (pin "2") (pinfunction "2_2") (pintype "passive"))
      (node (ref "D36") (pin "2") (pinfunction "2_2") (pintype "passive"))
      (node (ref "D37") (pin "2") (pinfunction "2_2") (pintype "passive"))
      (node (ref "D38") (pin "2") (pinfunction "2_2") (pintype "passive"))
      (node (ref "D39") (pin "2") (pinfunction "2_2") (pintype "passive"))
      (node (ref "D40") (pin "2") (pinfunction "2_2") (pintype "passive"))
      (node (ref "D41") (pin "2") (pinfunction "2_2") (pintype "passive"))
      (node (ref "D42") (pin "2") (pinfunction "2_2") (pintype "passive"))
      (node (ref "D43") (pin "2") (pinfunction "2_2") (pintype "passive"))
      (node (ref "D44") (pin "2") (pinfunction "2_2") (pintype "passive"))
      (node (ref "IC1") (pin "29") (pinfunction "PB5_(PCINT5/OC1A/~{OC4B}/ADC)_29") (pintype "passive"))
    )
    (net (code "24") (name "/ROW3") (class "Default")
      (node (ref "D45") (pin "2") (pinfunction "2_2") (pintype "passive"))
      (node (ref "D46") (pin "2") (pinfunction "2_2") (pintype "passive"))
      (node (ref "D47") (pin "2") (pinfunction "2_2") (pintype "passive"))
      (node (ref "D48") (pin "2") (pinfunction "2_2") (pintype "passive"))
      (node (ref "D49") (pin "2") (pinfunction "2_2") (pintype "passive"))
      (node (ref "D50") (pin "2") (pinfunction "2_2") (pintype "passive"))
      (node (ref "D51") (pin "2") (pinfunction "2_2") (pintype "passive"))
      (node (ref "D52") (pin "2") (pinfunction "2_2") (pintype "passive"))
      (node (ref "D53") (pin "2") (pinfunction "2_2") (pintype "passive"))
      (node (ref "D54") (pin "2") (pinfunction "2_2") (pintype "passive"))
      (node (ref "D55") (pin "2") (pinfunction "2_2") (pintype "passive"))
      (node (ref "D56") (pin "2") (pinfunction "2_2") (pintype "passive"))
      (node (ref "D57") (pin "2") (pinfunction "2_2") (pintype "passive"))
      (node (ref "D58") (pin "2") (pinfunction "2_2") (pintype "passive"))
      (node (ref "IC1") (pin "12") (pinfunction "(PCINT7/OC0A/OC1C/~{RTS)_PB7}_12") (pintype "passive"))
    )
    (net (code "25") (name "/ROW4") (class "Default")
      (node (ref "D59") (pin "2") (pinfunction "2_2") (pintype "passive"))
      (node (ref "D60") (pin "2") (pinfunction "2_2") (pintype "passive"))
      (node (ref "D61") (pin "2") (pinfunction "2_2") (pintype "passive"))
      (node (ref "D62") (pin "2") (pinfunction "2_2") (pintype "passive"))
      (node (ref "D63") (pin "2") (pinfunction "2_2") (pintype "passive"))
      (node (ref "D64") (pin "2") (pinfunction "2_2") (pintype "passive"))
      (node (ref "D65") (pin "2") (pinfunction "2_2") (pintype "passive"))
      (node (ref "D66") (pin "2") (pinfunction "2_2") (pintype "passive"))
      (node (ref "D67") (pin "2") (pinfunction "2_2") (pintype "passive"))
      (node (ref "IC1") (pin "36") (pinfunction "PF7_(ADC7/TDI)_36") (pintype "passive"))
    )
    (net (code "26") (name "/SCK") (class "Default")
      (node (ref "IC1") (pin "9") (pinfunction "(PCINT1/SCLK)_PB1_9") (pintype "passive"))
      (node (ref "J2") (pin "2") (pintype "passive"))
    )
    (net (code "27") (name "/USB_N") (class "Default")
      (node (ref "IC1") (pin "3") (pinfunction "D-_3") (pintype "passive"))
      (node (ref "R3") (pin "2") (pinfunction "2_2") (pintype "passive"))
    )
    (net (code "28") (name "/USB_P") (class "Default")
      (node (ref "IC1") (pin "4") (pinfunction "D+_4") (pintype "passive"))
      (node (ref "R2") (pin "1") (pinfunction "1_1") (pintype "passive"))
    )
    (net (code "29") (name "/VBUS") (class "Default")
      (node (ref "C1") (pin "2") (pinfunction "2_2") (pintype "passive"))
      (node (ref "C2") (pin "2") (pinfunction "2_2") (pintype "passive"))
      (node (ref "C3") (pin "2") (pinfunction "2_2") (pintype "passive"))
      (node (ref "C4") (pin "2") (pinfunction "2_2") (pintype "passive"))
      (node (ref "C5") (pin "2") (pinfunction "2_2") (pintype "passive"))
      (node (ref "D68") (pin "5") (pinfunction "REF_5") (pintype "passive"))
      (node (ref "IC1") (pin "14") (pinfunction "VCC_1_14") (pintype "passive"))
      (node (ref "IC1") (pin "2") (pinfunction "UVCC_2") (pintype "passive"))
      (node (ref "IC1") (pin "24") (pinfunction "AVCC_1_24") (pintype "passive"))
      (node (ref "IC1") (pin "34") (pinfunction "VCC_2_34") (pintype "passive"))
      (node (ref "IC1") (pin "44") (pinfunction "AVCC_2_44") (pintype "passive"))
      (node (ref "IC1") (pin "7") (pinfunction "VBUS_7") (pintype "passive"))
      (node (ref "J1") (pin "1") (pinfunction "1_1") (pintype "passive"))
      (node (ref "J2") (pin "1") (pintype "passive"))
      (node (ref "R4") (pin "2") (pinfunction "2_2") (pintype "passive"))
    )
    (net (code "30") (name "/XTAL1") (class "Default")
      (node (ref "C8") (pin "1") (pinfunction "1_1") (pintype "passive"))
      (node (ref "IC1") (pin "17") (pinfunction "XTAL1_17") (pintype "passive"))
      (node (ref "Y1") (pin "1") (pinfunction "1_1") (pintype "passive"))
    )
    (net (code "31") (name "/XTAL2") (class "Default")
      (node (ref "C6") (pin "1") (pinfunction "1_1") (pintype "passive"))
      (node (ref "IC1") (pin "16") (pinfunction "XTAL2_16") (pintype "passive"))
      (node (ref "Y1") (pin "3") (pinfunction "3_3") (pintype "passive"))
    )
    (net (code "32") (name "GND") (class "Default")
      (node (ref "C1") (pin "1") (pinfunction "1_1") (pintype "passive"))
      (node (ref "C2") (pin "1") (pinfunction "1_1") (pintype "passive"))
      (node (ref "C3") (pin "1") (pinfunction "1_1") (pintype "passive"))
      (node (ref "C4") (pin "1") (pinfunction "1_1") (pintype "passive"))
      (node (ref "C5") (pin "1") (pinfunction "1_1") (pintype "passive"))
      (node (ref "C6") (pin "2") (pinfunction "2_2") (pintype "passive"))
      (node (ref "C7") (pin "1") (pinfunction "1_1") (pintype "passive"))
      (node (ref "C8") (pin "2") (pinfunction "2_2") (pintype "passive"))
      (node (ref "D68") (pin "2") (pinfunction "GND_2") (pintype "passive"))
      (node (ref "IC1") (pin "15") (pinfunction "GND_1_15") (pintype "passive"))
      (node (ref "IC1") (pin "23") (pinfunction "GND_2_23") (pintype "passive"))
      (node (ref "IC1") (pin "35") (pinfunction "GND_3_35") (pintype "passive"))
      (node (ref "IC1") (pin "43") (pinfunction "GND_4_43") (pintype "passive"))
      (node (ref "IC1") (pin "5") (pinfunction "UGND_5") (pintype "passive"))
      (node (ref "J1") (pin "4") (pinfunction "4_4") (pintype "passive"))
      (node (ref "J2") (pin "6") (pintype "passive"))
      (node (ref "R1") (pin "2") (pinfunction "2_2") (pintype "passive"))
      (node (ref "SW68") (pin "2") (pinfunction "8_2") (pintype "passive"))
      (node (ref "Y1") (pin "2") (pinfunction "2_2") (pintype "passive"))
      (node (ref "Y1") (pin "4") (pinfunction "4_4") (pintype "passive"))
    )
    (net (code "33") (name "Net-(D1-+)") (class "Default")
      (node (ref "D1") (pin "1") (pinfunction "+_1") (pintype "passive"))
      (node (ref "SW1") (pin "2") (pinfunction "8_2") (pintype "passive"))
    )
    (net (code "34") (name "Net-(D2-+)") (class "Default")
      (node (ref "D2") (pin "1") (pinfunction "+_1") (pintype "passive"))
      (node (ref "SW2") (pin "2") (pinfunction "8_2") (pintype "passive"))
    )
    (net (code "35") (name "Net-(D3-+)") (class "Default")
      (node (ref "D3") (pin "1") (pinfunction "+_1") (pintype "passive"))
      (node (ref "SW3") (pin "2") (pinfunction "8_2") (pintype "passive"))
    )
    (net (code "36") (name "Net-(D4-+)") (class "Default")
      (node (ref "D4") (pin "1") (pinfunction "+_1") (pintype "passive"))
      (node (ref "SW4") (pin "2") (pinfunction "8_2") (pintype "passive"))
    )
    (net (code "37") (name "Net-(D5-+)") (class "Default")
      (node (ref "D5") (pin "1") (pinfunction "+_1") (pintype "passive"))
      (node (ref "SW5") (pin "2") (pinfunction "8_2") (pintype "passive"))
    )
    (net (code "38") (name "Net-(D6-+)") (class "Default")
      (node (ref "D6") (pin "1") (pinfunction "+_1") (pintype "passive"))
      (node (ref "SW6") (pin "2") (pinfunction "8_2") (pintype "passive"))
    )
    (net (code "39") (name "Net-(D7-+)") (class "Default")
      (node (ref "D7") (pin "1") (pinfunction "+_1") (pintype "passive"))
      (node (ref "SW7") (pin "2") (pinfunction "8_2") (pintype "passive"))
    )
    (net (code "40") (name "Net-(D8-+)") (class "Default")
      (node (ref "D8") (pin "1") (pinfunction "+_1") (pintype "passive"))
      (node (ref "SW8") (pin "2") (pinfunction "8_2") (pintype "passive"))
    )
    (net (code "41") (name "Net-(D9-+)") (class "Default")
      (node (ref "D9") (pin "1") (pinfunction "+_1") (pintype "passive"))
      (node (ref "SW9") (pin "2") (pinfunction "8_2") (pintype "passive"))
    )
    (net (code "42") (name "Net-(D10-+)") (class "Default")
      (node (ref "D10") (pin "1") (pinfunction "+_1") (pintype "passive"))
      (node (ref "SW10") (pin "2") (pinfunction "8_2") (pintype "passive"))
    )
    (net (code "43") (name "Net-(D11-+)") (class "Default")
      (node (ref "D11") (pin "1") (pinfunction "+_1") (pintype "passive"))
      (node (ref "SW11") (pin "2") (pinfunction "8_2") (pintype "passive"))
    )
    (net (code "44") (name "Net-(D12-+)") (class "Default")
      (node (ref "D12") (pin "1") (pinfunction "+_1") (pintype "passive"))
      (node (ref "SW12") (pin "2") (pinfunction "8_2") (pintype "passive"))
    )
    (net (code "45") (name "Net-(D13-+)") (class "Default")
      (node (ref "D13") (pin "1") (pinfunction "+_1") (pintype "passive"))
      (node (ref "SW13") (pin "2") (pinfunction "8_2") (pintype "passive"))
    )
    (net (code "46") (name "Net-(D14-+)") (class "Default")
      (node (ref "D14") (pin "1") (pinfunction "+_1") (pintype "passive"))
      (node (ref "SW14") (pin "2") (pinfunction "8_2") (pintype "passive"))
    )
    (net (code "47") (name "Net-(D15-+)") (class "Default")
      (node (ref "D15") (pin "1") (pinfunction "+_1") (pintype "passive"))
      (node (ref "SW15") (pin "2") (pinfunction "8_2") (pintype "passive"))
    )
    (net (code "48") (name "Net-(D16-+)") (class "Default")
      (node (ref "D16") (pin "1") (pinfunction "+_1") (pintype "passive"))
      (node (ref "SW16") (pin "2") (pinfunction "8_2") (pintype "passive"))
    )
    (net (code "49") (name "Net-(D17-+)") (class "Default")
      (node (ref "D17") (pin "1") (pinfunction "+_1") (pintype "passive"))
      (node (ref "SW17") (pin "2") (pinfunction "8_2") (pintype "passive"))
    )
    (net (code "50") (name "Net-(D18-+)") (class "Default")
      (node (ref "D18") (pin "1") (pinfunction "+_1") (pintype "passive"))
      (node (ref "SW18") (pin "2") (pinfunction "8_2") (pintype "passive"))
    )
    (net (code "51") (name "Net-(D19-+)") (class "Default")
      (node (ref "D19") (pin "1") (pinfunction "+_1") (pintype "passive"))
      (node (ref "SW19") (pin "2") (pinfunction "8_2") (pintype "passive"))
    )
    (net (code "52") (name "Net-(D20-+)") (class "Default")
      (node (ref "D20") (pin "1") (pinfunction "+_1") (pintype "passive"))
      (node (ref "SW20") (pin "2") (pinfunction "8_2") (pintype "passive"))
    )
    (net (code "53") (name "Net-(D21-+)") (class "Default")
      (node (ref "D21") (pin "1") (pinfunction "+_1") (pintype "passive"))
      (node (ref "SW21") (pin "2") (pinfunction "8_2") (pintype "passive"))
    )
    (net (code "54") (name "Net-(D22-+)") (class "Default")
      (node (ref "D22") (pin "1") (pinfunction "+_1") (pintype "passive"))
      (node (ref "SW22") (pin "2") (pinfunction "8_2") (pintype "passive"))
    )
    (net (code "55") (name "Net-(D23-+)") (class "Default")
      (node (ref "D23") (pin "1") (pinfunction "+_1") (pintype "passive"))
      (node (ref "SW23") (pin "2") (pinfunction "8_2") (pintype "passive"))
    )
    (net (code "56") (name "Net-(D24-+)") (class "Default")
      (node (ref "D24") (pin "1") (pinfunction "+_1") (pintype "passive"))
      (node (ref "SW24") (pin "2") (pinfunction "8_2") (pintype "passive"))
    )
    (net (code "57") (name "Net-(D25-+)") (class "Default")
      (node (ref "D25") (pin "1") (pinfunction "+_1") (pintype "passive"))
      (node (ref "SW25") (pin "2") (pinfunction "8_2") (pintype "passive"))
    )
    (net (code "58") (name "Net-(D26-+)") (class "Default")
      (node (ref "D26") (pin "1") (pinfunction "+_1") (pintype "passive"))
      (node (ref "SW26") (pin "2") (pinfunction "8_2") (pintype "passive"))
    )
    (net (code "59") (name "Net-(D27-+)") (class "Default")
      (node (ref "D27") (pin "1") (pinfunction "+_1") (pintype "passive"))
      (node (ref "SW27") (pin "2") (pinfunction "8_2") (pintype "passive"))
    )
    (net (code "60") (name "Net-(D28-+)") (class "Default")
      (node (ref "D28") (pin "1") (pinfunction "+_1") (pintype "passive"))
      (node (ref "SW28") (pin "2") (pinfunction "8_2") (pintype "passive"))
    )
    (net (code "61") (name "Net-(D29-+)") (class "Default")
      (node (ref "D29") (pin "1") (pinfunction "+_1") (pintype "passive"))
      (node (ref "SW29") (pin "2") (pinfunction "8_2") (pintype "passive"))
    )
    (net (code "62") (name "Net-(D30-+)") (class "Default")
      (node (ref "D30") (pin "1") (pinfunction "+_1") (pintype "passive"))
      (node (ref "SW30") (pin "2") (pinfunction "8_2") (pintype "passive"))
    )
    (net (code "63") (name "Net-(D31-+)") (class "Default")
      (node (ref "D31") (pin "1") (pinfunction "+_1") (pintype "passive"))
      (node (ref "SW31") (pin "2") (pinfunction "8_2") (pintype "passive"))
    )
    (net (code "64") (name "Net-(D32-+)") (class "Default")
      (node (ref "D32") (pin "1") (pinfunction "+_1") (pintype "passive"))
      (node (ref "SW32") (pin "2") (pinfunction "8_2") (pintype "passive"))
    )
    (net (code "65") (name "Net-(D33-+)") (class "Default")
      (node (ref "D33") (pin "1") (pinfunction "+_1") (pintype "passive"))
      (node (ref "SW33") (pin "2") (pinfunction "8_2") (pintype "passive"))
    )
    (net (code "66") (name "Net-(D34-+)") (class "Default")
      (node (ref "D34") (pin "1") (pinfunction "+_1") (pintype "passive"))
      (node (ref "SW34") (pin "2") (pinfunction "8_2") (pintype "passive"))
    )
    (net (code "67") (name "Net-(D35-+)") (class "Default")
      (node (ref "D35") (pin "1") (pinfunction "+_1") (pintype "passive"))
      (node (ref "SW35") (pin "2") (pinfunction "8_2") (pintype "passive"))
    )
    (net (code "68") (name "Net-(D36-+)") (class "Default")
      (node (ref "D36") (pin "1") (pinfunction "+_1") (pintype "passive"))
      (node (ref "SW36") (pin "2") (pinfunction "8_2") (pintype "passive"))
    )
    (net (code "69") (name "Net-(D37-+)") (class "Default")
      (node (ref "D37") (pin "1") (pinfunction "+_1") (pintype "passive"))
      (node (ref "SW37") (pin "2") (pinfunction "8_2") (pintype "passive"))
    )
    (net (code "70") (name "Net-(D38-+)") (class "Default")
      (node (ref "D38") (pin "1") (pinfunction "+_1") (pintype "passive"))
      (node (ref "SW38") (pin "2") (pinfunction "8_2") (pintype "passive"))
    )
    (net (code "71") (name "Net-(D39-+)") (class "Default")
      (node (ref "D39") (pin "1") (pinfunction "+_1") (pintype "passive"))
      (node (ref "SW39") (pin "2") (pinfunction "8_2") (pintype "passive"))
    )
    (net (code "72") (name "Net-(D40-+)") (class "Default")
      (node (ref "D40") (pin "1") (pinfunction "+_1") (pintype "passive"))
      (node (ref "SW40") (pin "2") (pinfunction "8_2") (pintype "passive"))
    )
    (net (code "73") (name "Net-(D41-+)") (class "Default")
      (node (ref "D41") (pin "1") (pinfunction "+_1") (pintype "passive"))
      (node (ref "SW41") (pin "2") (pinfunction "8_2") (pintype "passive"))
    )
    (net (code "74") (name "Net-(D42-+)") (class "Default")
      (node (ref "D42") (pin "1") (pinfunction "+_1") (pintype "passive"))
      (node (ref "SW42") (pin "2") (pinfunction "8_2") (pintype "passive"))
    )
    (net (code "75") (name "Net-(D43-+)") (class "Default")
      (node (ref "D43") (pin "1") (pinfunction "+_1") (pintype "passive"))
      (node (ref "SW43") (pin "2") (pinfunction "8_2") (pintype "passive"))
    )
    (net (code "76") (name "Net-(D44-+)") (class "Default")
      (node (ref "D44") (pin "1") (pinfunction "+_1") (pintype "passive"))
      (node (ref "SW44") (pin "2") (pinfunction "8_2") (pintype "passive"))
    )
    (net (code "77") (name "Net-(D45-+)") (class "Default")
      (node (ref "D45") (pin "1") (pinfunction "+_1") (pintype "passive"))
      (node (ref "SW45") (pin "2") (pinfunction "8_2") (pintype "passive"))
    )
    (net (code "78") (name "Net-(D46-+)") (class "Default")
      (node (ref "D46") (pin "1") (pinfunction "+_1") (pintype "passive"))
      (node (ref "SW46") (pin "2") (pinfunction "8_2") (pintype "passive"))
    )
    (net (code "79") (name "Net-(D47-+)") (class "Default")
      (node (ref "D47") (pin "1") (pinfunction "+_1") (pintype "passive"))
      (node (ref "SW47") (pin "2") (pinfunction "8_2") (pintype "passive"))
    )
    (net (code "80") (name "Net-(D48-+)") (class "Default")
      (node (ref "D48") (pin "1") (pinfunction "+_1") (pintype "passive"))
      (node (ref "SW48") (pin "2") (pinfunction "8_2") (pintype "passive"))
    )
    (net (code "81") (name "Net-(D49-+)") (class "Default")
      (node (ref "D49") (pin "1") (pinfunction "+_1") (pintype "passive"))
      (node (ref "SW49") (pin "2") (pinfunction "8_2") (pintype "passive"))
    )
    (net (code "82") (name "Net-(D50-+)") (class "Default")
      (node (ref "D50") (pin "1") (pinfunction "+_1") (pintype "passive"))
      (node (ref "SW50") (pin "2") (pinfunction "8_2") (pintype "passive"))
    )
    (net (code "83") (name "Net-(D51-+)") (class "Default")
      (node (ref "D51") (pin "1") (pinfunction "+_1") (pintype "passive"))
      (node (ref "SW51") (pin "2") (pinfunction "8_2") (pintype "passive"))
    )
    (net (code "84") (name "Net-(D52-+)") (class "Default")
      (node (ref "D52") (pin "1") (pinfunction "+_1") (pintype "passive"))
      (node (ref "SW52") (pin "2") (pinfunction "8_2") (pintype "passive"))
    )
    (net (code "85") (name "Net-(D53-+)") (class "Default")
      (node (ref "D53") (pin "1") (pinfunction "+_1") (pintype "passive"))
      (node (ref "SW53") (pin "2") (pinfunction "8_2") (pintype "passive"))
    )
    (net (code "86") (name "Net-(D54-+)") (class "Default")
      (node (ref "D54") (pin "1") (pinfunction "+_1") (pintype "passive"))
      (node (ref "SW54") (pin "2") (pinfunction "8_2") (pintype "passive"))
    )
    (net (code "87") (name "Net-(D55-+)") (class "Default")
      (node (ref "D55") (pin "1") (pinfunction "+_1") (pintype "passive"))
      (node (ref "SW55") (pin "2") (pinfunction "8_2") (pintype "passive"))
    )
    (net (code "88") (name "Net-(D56-+)") (class "Default")
      (node (ref "D56") (pin "1") (pinfunction "+_1") (pintype "passive"))
      (node (ref "SW56") (pin "2") (pinfunction "8_2") (pintype "passive"))
    )
    (net (code "89") (name "Net-(D57-+)") (class "Default")
      (node (ref "D57") (pin "1") (pinfunction "+_1") (pintype "passive"))
      (node (ref "SW57") (pin "2") (pinfunction "8_2") (pintype "passive"))
    )
    (net (code "90") (name "Net-(D58-+)") (class "Default")
      (node (ref "D58") (pin "1") (pinfunction "+_1") (pintype "passive"))
      (node (ref "SW58") (pin "2") (pinfunction "8_2") (pintype "passive"))
    )
    (net (code "91") (name "Net-(D59-+)") (class "Default")
      (node (ref "D59") (pin "1") (pinfunction "+_1") (pintype "passive"))
      (node (ref "SW59") (pin "2") (pinfunction "8_2") (pintype "passive"))
    )
    (net (code "92") (name "Net-(D60-+)") (class "Default")
      (node (ref "D60") (pin "1") (pinfunction "+_1") (pintype "passive"))
      (node (ref "SW60") (pin "2") (pinfunction "8_2") (pintype "passive"))
    )
    (net (code "93") (name "Net-(D61-+)") (class "Default")
      (node (ref "D61") (pin "1") (pinfunction "+_1") (pintype "passive"))
      (node (ref "SW61") (pin "2") (pinfunction "8_2") (pintype "passive"))
    )
    (net (code "94") (name "Net-(D62-+)") (class "Default")
      (node (ref "D62") (pin "1") (pinfunction "+_1") (pintype "passive"))
      (node (ref "SW62") (pin "2") (pinfunction "8_2") (pintype "passive"))
    )
    (net (code "95") (name "Net-(D63-+)") (class "Default")
      (node (ref "D63") (pin "1") (pinfunction "+_1") (pintype "passive"))
      (node (ref "SW63") (pin "2") (pinfunction "8_2") (pintype "passive"))
    )
    (net (code "96") (name "Net-(D64-+)") (class "Default")
      (node (ref "D64") (pin "1") (pinfunction "+_1") (pintype "passive"))
      (node (ref "SW64") (pin "2") (pinfunction "8_2") (pintype "passive"))
    )
    (net (code "97") (name "Net-(D65-+)") (class "Default")
      (node (ref "D65") (pin "1") (pinfunction "+_1") (pintype "passive"))
      (node (ref "SW65") (pin "2") (pinfunction "8_2") (pintype "passive"))
    )
    (net (code "98") (name "Net-(D66-+)") (class "Default")
      (node (ref "D66") (pin "1") (pinfunction "+_1") (pintype "passive"))
      (node (ref "SW66") (pin "2") (pinfunction "8_2") (pintype "passive"))
    )
    (net (code "99") (name "Net-(D67-+)") (class "Default")
      (node (ref "D67") (pin "1") (pinfunction "+_1") (pintype "passive"))
      (node (ref "SW67") (pin "2") (pinfunction "8_2") (pintype "passive"))
    )
    (net (code "100") (name "Net-(IC1-PE2_(~{HWB)})") (class "Default")
      (node (ref "IC1") (pin "33") (pinfunction "PE2_(~{HWB)}_33") (pintype "passive"))
      (node (ref "R1") (pin "1") (pinfunction "1_1") (pintype "passive"))
    )
    (net (code "101") (name "Net-(IC1-UCAP)") (class "Default")
      (node (ref "C7") (pin "2") (pinfunction "2_2") (pintype "passive"))
      (node (ref "IC1") (pin "6") (pinfunction "UCAP_6") (pintype "passive"))
    )
    (net (code "102") (name "unconnected-(D68-I{slash}O_2-Pad3)") (class "Default")
      (node (ref "D68") (pin "3") (pinfunction "I/O_2_3") (pintype "passive"))
    )
    (net (code "103") (name "unconnected-(D68-I{slash}O_3-Pad4)") (class "Default")
      (node (ref "D68") (pin "4") (pinfunction "I/O_3_4") (pintype "passive"))
    )
    (net (code "104") (name "unconnected-(IC1-(INT.6{slash}AIN0)_PE6-Pad1)") (class "Default")
      (node (ref "IC1") (pin "1") (pinfunction "(INT.6/AIN0)_PE6_1") (pintype "passive"))
    )
    (net (code "105") (name "unconnected-(IC1-AREF-Pad42)") (class "Default")
      (node (ref "IC1") (pin "42") (pinfunction "AREF_42") (pintype "passive"))
    )
    (net (code "106") (name "unconnected-(IC1-PF0_(ADC0)-Pad41)") (class "Default")
      (node (ref "IC1") (pin "41") (pinfunction "PF0_(ADC0)_41") (pintype "passive"))
    )
  )
)
